# Switches.net
KiCad netlist of a schematic drawn in Altium Designer
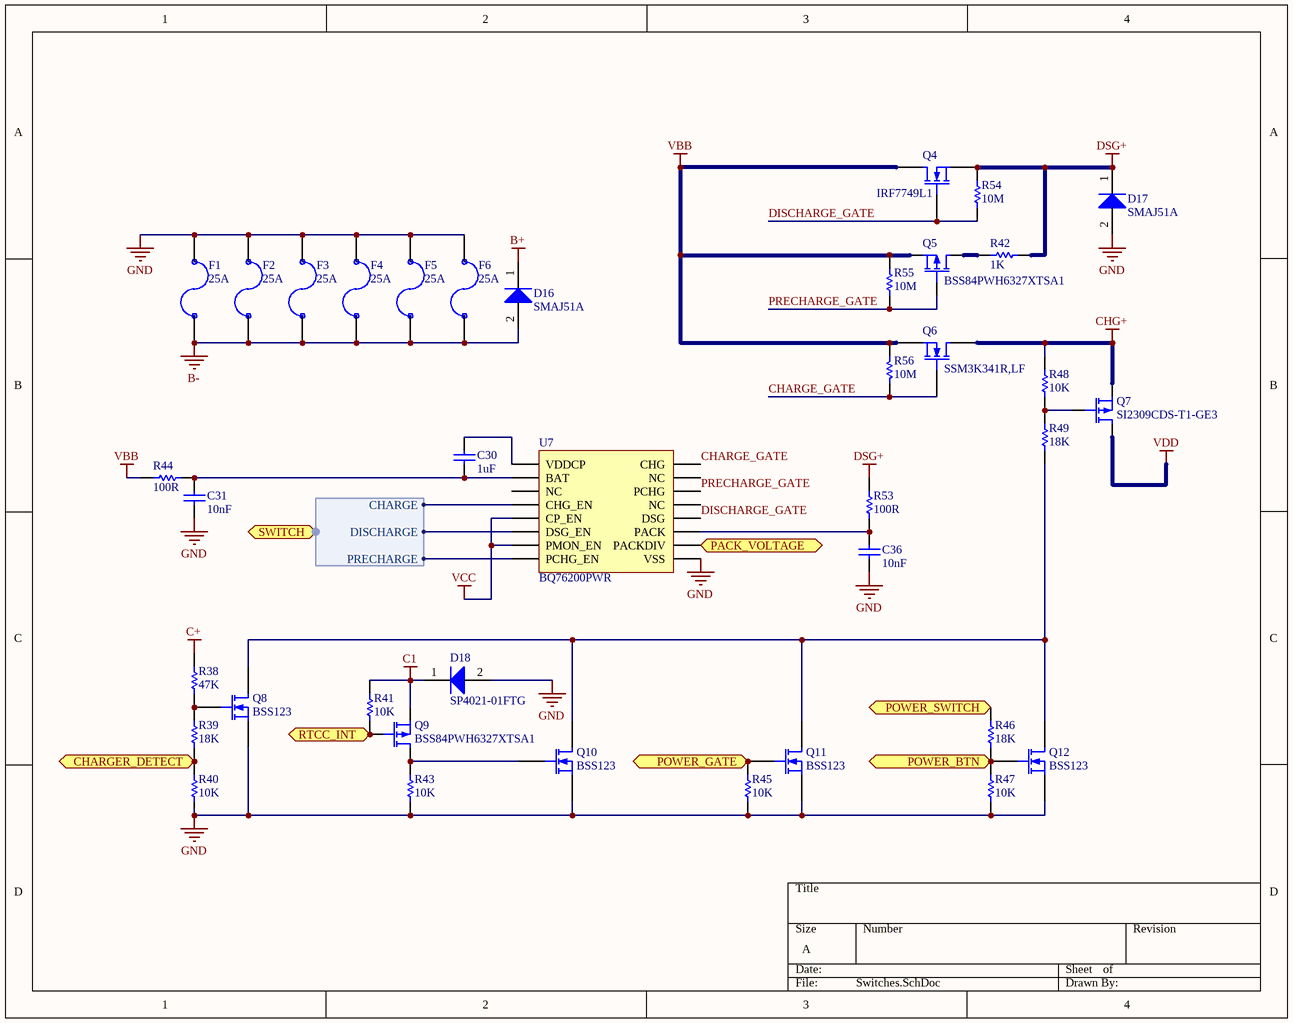
[diagram p0: Switches.SchDoc]

(export (version "E")
  (design (tool "Eeschema 10.0.6"))
  (components
    (comp (ref "C30")
      (value "1uF")
      (footprint "C0603[1608X92]")
      (description "1uF 50V 10% 0603 (1608 Metric)")
      (fields (field (name "TOLERANCE") "10%") (field (name "PARTNUMBER") "GRM188R61H105KAALD"))
      (libsource (lib "Capacitors") (part "CAP_1uF_50V_0603_10%"))
    )
    (comp (ref "C31")
      (value "10nF")
      (footprint "C0402[1005X55]")
      (description "10nF 50V 10% 0402 (1005 Metric)")
      (fields (field (name "TOLERANCE") "10%") (field (name "PARTNUMBER") "GCM155R71H103KA55D"))
      (libsource (lib "Capacitors") (part "CAP_10nF_50V_0402_10%"))
    )
    (comp (ref "C36")
      (value "10nF")
      (footprint "C0402[1005X55]")
      (description "10nF 50V 10% 0402 (1005 Metric)")
      (fields (field (name "TOLERANCE") "10%") (field (name "PARTNUMBER") "GCM155R71H103KA55D"))
      (libsource (lib "Capacitors") (part "CAP_10nF_50V_0402_10%"))
    )
    (comp (ref "D16")
      (value "SMAJ51A")
      (footprint "DO-214AC")
      (fields (field (name "PARTNUMBER") "SMAJ51A-E3/61") (field (name "MANUFACTURER") "Vishay"))
      (libsource (lib "Diodes") (part "SMAJ51A-E3/61"))
    )
    (comp (ref "D17")
      (value "SMAJ51A")
      (footprint "DO-214AC")
      (fields (field (name "PARTNUMBER") "SMAJ51A-E3/61") (field (name "MANUFACTURER") "Vishay"))
      (libsource (lib "Diodes") (part "SMAJ51A-E3/61"))
    )
    (comp (ref "D18")
      (value "SP4021-01FTG")
      (footprint "SOD-323")
      (fields (field (name "MANUFACTURER") "Littelfuse"))
      (libsource (lib "Diodes-TVS") (part "SP4021-01FTG"))
    )
    (comp (ref "F1")
      (value "FUSE 1206")
      (footprint "1206_FUSE")
      (description "Surface Mount Fuses UST 1206 FUSE 25A F")
      (fields
        (field (name "PARTNUMBER") "3413.0332.22")
        (field (name "MANUFACTURER") "Schurter")
        (field (name "CURRENT") "25A")
      )
      (libsource (lib "Components") (part "FUSE 1206"))
    )
    (comp (ref "F2")
      (value "FUSE 1206")
      (footprint "1206_FUSE")
      (description "Surface Mount Fuses UST 1206 FUSE 25A F")
      (fields
        (field (name "PARTNUMBER") "3413.0332.22")
        (field (name "MANUFACTURER") "Schurter")
        (field (name "CURRENT") "25A")
      )
      (libsource (lib "Components") (part "FUSE 1206"))
    )
    (comp (ref "F3")
      (value "FUSE 1206")
      (footprint "1206_FUSE")
      (description "Surface Mount Fuses UST 1206 FUSE 25A F")
      (fields
        (field (name "PARTNUMBER") "3413.0332.22")
        (field (name "MANUFACTURER") "Schurter")
        (field (name "CURRENT") "25A")
      )
      (libsource (lib "Components") (part "FUSE 1206"))
    )
    (comp (ref "F4")
      (value "FUSE 1206")
      (footprint "1206_FUSE")
      (description "Surface Mount Fuses UST 1206 FUSE 25A F")
      (fields
        (field (name "PARTNUMBER") "3413.0332.22")
        (field (name "MANUFACTURER") "Schurter")
        (field (name "CURRENT") "25A")
      )
      (libsource (lib "Components") (part "FUSE 1206"))
    )
    (comp (ref "F5")
      (value "FUSE 1206")
      (footprint "1206_FUSE")
      (description "Surface Mount Fuses UST 1206 FUSE 25A F")
      (fields
        (field (name "PARTNUMBER") "3413.0332.22")
        (field (name "MANUFACTURER") "Schurter")
        (field (name "CURRENT") "25A")
      )
      (libsource (lib "Components") (part "FUSE 1206"))
    )
    (comp (ref "F6")
      (value "FUSE 1206")
      (footprint "1206_FUSE")
      (description "Surface Mount Fuses UST 1206 FUSE 25A F")
      (fields
        (field (name "PARTNUMBER") "3413.0332.22")
        (field (name "MANUFACTURER") "Schurter")
        (field (name "CURRENT") "25A")
      )
      (libsource (lib "Components") (part "FUSE 1206"))
    )
    (comp (ref "Q4")
      (value "IRF7749L1")
      (footprint "DIRECTFET-9")
      (description "N-Channel MOSFET")
      (fields
        (field (name "PARTNUMBER") "IRF7749L1TRPBF")
        (field (name "MANUFACTURER") "Infineon Technologies")
      )
      (libsource (lib "MOSFETs") (part "IRF7749L2"))
    )
    (comp (ref "Q5")
      (value "BSS84PWH6327XTSA1")
      (footprint "SOT323-3")
      (description "P-Channel MOSFET")
      (fields (field (name "MANUFACTURER") "Infineon"))
      (libsource (lib "MOSFETs") (part "BSS84PW H6327"))
    )
    (comp (ref "Q6")
      (value "SSM3K341R,LF")
      (footprint "SOT23-3")
      (description "N-Channel MOSFET")
      (fields (field (name "MANUFACTURER") "Toshiba"))
      (libsource (lib "MOSFETs") (part "SSM3K341R,LF"))
    )
    (comp (ref "Q7")
      (value "SI2309CDS-T1-GE3")
      (footprint "SOT23-3")
      (description "P-Channel MOSFET")
      (fields (field (name "MANUFACTURER") "Vishay"))
      (libsource (lib "MOSFETs") (part "SI2309CDS-T1-GE3"))
    )
    (comp (ref "Q8")
      (value "BSS123")
      (footprint "SOT323-3")
      (description "N-Channel MOSFET")
      (fields (field (name "PARTNUMBER") "BSS123WQ-7-F") (field (name "MANUFACTURER") "Diodes Incorporated"))
      (libsource (lib "MOSFETs") (part "BSS123WQ-7-F"))
    )
    (comp (ref "Q9")
      (value "BSS84PWH6327XTSA1")
      (footprint "SOT323-3")
      (description "P-Channel MOSFET")
      (fields (field (name "MANUFACTURER") "Infineon"))
      (libsource (lib "MOSFETs") (part "BSS84PW H6327"))
    )
    (comp (ref "Q10")
      (value "BSS123")
      (footprint "SOT323-3")
      (description "N-Channel MOSFET")
      (fields (field (name "PARTNUMBER") "BSS123WQ-7-F") (field (name "MANUFACTURER") "Diodes Incorporated"))
      (libsource (lib "MOSFETs") (part "BSS123WQ-7-F"))
    )
    (comp (ref "Q11")
      (value "BSS123")
      (footprint "SOT323-3")
      (description "N-Channel MOSFET")
      (fields (field (name "PARTNUMBER") "BSS123WQ-7-F") (field (name "MANUFACTURER") "Diodes Incorporated"))
      (libsource (lib "MOSFETs") (part "BSS123WQ-7-F"))
    )
    (comp (ref "Q12")
      (value "BSS123")
      (footprint "SOT323-3")
      (description "N-Channel MOSFET")
      (fields (field (name "PARTNUMBER") "BSS123WQ-7-F") (field (name "MANUFACTURER") "Diodes Incorporated"))
      (libsource (lib "MOSFETs") (part "BSS123WQ-7-F"))
    )
    (comp (ref "R38")
      (value "47K")
      (footprint "R0402[1005]")
      (description "47K 0.063W 1% 0402 (1005 Metric)")
      (fields (field (name "POWER") "0.063W") (field (name "TOLERANCE") "1%"))
      (libsource (lib "Resistors") (part "RES_47K_0402_1%"))
    )
    (comp (ref "R39")
      (value "18K")
      (footprint "R0402[1005]")
      (description "18K 0.063W 1% 0402 (1005 Metric)")
      (fields (field (name "TOLERANCE") "1%") (field (name "POWER") "0.063W"))
      (libsource (lib "Resistors") (part "RES_18K_0402_1%"))
    )
    (comp (ref "R40")
      (value "10K")
      (footprint "R0402[1005]")
      (description "10K 0.063W 1% 0402 (1005 Metric)")
      (fields (field (name "TOLERANCE") "1%") (field (name "POWER") "0.063W"))
      (libsource (lib "Resistors") (part "RES_10K_0402_1%"))
    )
    (comp (ref "R41")
      (value "10K")
      (footprint "R0402[1005]")
      (description "10K 0.063W 1% 0402 (1005 Metric)")
      (fields (field (name "MANUFACTURER") "KOA Speer") (field (name "PARTNUMBER") "RK73H1ETTP1002F"))
      (libsource (lib "Resistors") (part "RES_10K_0402_1%"))
    )
    (comp (ref "R42")
      (value "1K")
      (footprint "R0805[2012]")
      (description "1K 0.5W 1% 0805 (2012 Metric)")
      (fields (field (name "TOLERANCE") "1%") (field (name "POWER") "0.5W"))
      (libsource (lib "Resistors") (part "RES_1K_0805_1%"))
    )
    (comp (ref "R43")
      (value "10K")
      (footprint "R0402[1005]")
      (description "10K 0.063W 1% 0402 (1005 Metric)")
      (fields (field (name "MANUFACTURER") "KOA Speer") (field (name "PARTNUMBER") "RK73H1ETTP1002F"))
      (libsource (lib "Resistors") (part "RES_10K_0402_1%"))
    )
    (comp (ref "R44")
      (value "100R")
      (footprint "R0402[1005]")
      (description "100R 0.063W 1% 0402 (1005 Metric)")
      (fields (field (name "POWER") "0.063W") (field (name "TOLERANCE") "1%"))
      (libsource (lib "Resistors") (part "RES_100R_0402_1%"))
    )
    (comp (ref "R45")
      (value "10K")
      (footprint "R0402[1005]")
      (description "10K 0.063W 1% 0402 (1005 Metric)")
      (fields (field (name "MANUFACTURER") "KOA Speer") (field (name "PARTNUMBER") "RK73H1ETTP1002F"))
      (libsource (lib "Resistors") (part "RES_10K_0402_1%"))
    )
    (comp (ref "R46")
      (value "18K")
      (footprint "R0402[1005]")
      (description "18K 0.063W 1% 0402 (1005 Metric)")
      (fields (field (name "TOLERANCE") "1%") (field (name "POWER") "0.063W"))
      (libsource (lib "Resistors") (part "RES_18K_0402_1%"))
    )
    (comp (ref "R47")
      (value "10K")
      (footprint "R0402[1005]")
      (description "10K 0.063W 1% 0402 (1005 Metric)")
      (fields (field (name "POWER") "0.063W") (field (name "TOLERANCE") "1%"))
      (libsource (lib "Resistors") (part "RES_10K_0402_1%"))
    )
    (comp (ref "R48")
      (value "10K")
      (footprint "R0402[1005]")
      (description "10K 0.063W 1% 0402 (1005 Metric)")
      (fields (field (name "TOLERANCE") "1%") (field (name "POWER") "0.063W"))
      (libsource (lib "Resistors") (part "RES_10K_0402_1%"))
    )
    (comp (ref "R49")
      (value "18K")
      (footprint "R0402[1005]")
      (description "18K 0.063W 1% 0402 (1005 Metric)")
      (fields (field (name "POWER") "0.063W") (field (name "TOLERANCE") "1%"))
      (libsource (lib "Resistors") (part "RES_18K_0402_1%"))
    )
    (comp (ref "R53")
      (value "100R")
      (footprint "R0402[1005]")
      (description "100R 0.063W 1% 0402 (1005 Metric)")
      (fields (field (name "POWER") "0.063W") (field (name "TOLERANCE") "1%"))
      (libsource (lib "Resistors") (part "RES_100R_0402_1%"))
    )
    (comp (ref "R54")
      (value "10M")
      (footprint "R0402[1005]")
      (description "10M 0.063W 1% 0402 (1005 Metric)")
      (fields (field (name "MANUFACTURER") "KOA Speer") (field (name "PARTNUMBER") "RK73H1ETTP1005F"))
      (libsource (lib "Resistors") (part "RES_10M_0402_1%"))
    )
    (comp (ref "R55")
      (value "10M")
      (footprint "R0402[1005]")
      (description "10M 0.063W 1% 0402 (1005 Metric)")
      (fields (field (name "MANUFACTURER") "KOA Speer") (field (name "PARTNUMBER") "RK73H1ETTP1005F"))
      (libsource (lib "Resistors") (part "RES_10M_0402_1%"))
    )
    (comp (ref "R56")
      (value "10M")
      (footprint "R0402[1005]")
      (description "10M 0.063W 1% 0402 (1005 Metric)")
      (fields (field (name "MANUFACTURER") "KOA Speer") (field (name "PARTNUMBER") "RK73H1ETTP1005F"))
      (libsource (lib "Resistors") (part "RES_10M_0402_1%"))
    )
    (comp (ref "U7")
      (value "BQ76200PWR")
      (footprint "TSSOP-16")
      (description "Battery Management Fast high side NCH drive")
      (fields (field (name "MANUFACTURER") "Texas Instruments"))
      (libsource (lib "ICs") (part "BQ76200PWR"))
    )
  )
  (nets
    (net (code "2") (name "/CHARGE") (class "Default")
      (node (ref "U7") (pin "4") (pinfunction "CHG_EN_4") (pintype "passive"))
    )
    (net (code "3") (name "/CHARGER_DETECT") (class "Default")
      (node (ref "R39") (pin "1") (pinfunction "1_1") (pintype "passive"))
      (node (ref "R40") (pin "2") (pinfunction "2_2") (pintype "passive"))
    )
    (net (code "4") (name "/CHARGE_GATE") (class "Default")
      (node (ref "Q6") (pin "1") (pinfunction "G_1") (pintype "passive"))
      (node (ref "R56") (pin "1") (pinfunction "1_1") (pintype "passive"))
      (node (ref "U7") (pin "16") (pinfunction "CHG_16") (pintype "passive"))
    )
    (net (code "5") (name "/DISCHARGE") (class "Default")
      (node (ref "U7") (pin "6") (pinfunction "DSG_EN_6") (pintype "passive"))
    )
    (net (code "6") (name "/DISCHARGE_GATE") (class "Default")
      (node (ref "Q4") (pin "1") (pinfunction "G_1") (pintype "passive"))
      (node (ref "R54") (pin "1") (pinfunction "1_1") (pintype "passive"))
      (node (ref "U7") (pin "12") (pinfunction "DSG_12") (pintype "passive"))
    )
    (net (code "7") (name "/PACK_VOLTAGE") (class "Default")
      (node (ref "U7") (pin "10") (pinfunction "PACKDIV_10") (pintype "passive"))
    )
    (net (code "8") (name "/POWER_BTN") (class "Default")
      (node (ref "Q12") (pin "1") (pinfunction "G_1") (pintype "passive"))
      (node (ref "R46") (pin "1") (pinfunction "1_1") (pintype "passive"))
      (node (ref "R47") (pin "2") (pinfunction "2_2") (pintype "passive"))
    )
    (net (code "9") (name "/POWER_GATE") (class "Default")
      (node (ref "Q11") (pin "1") (pinfunction "G_1") (pintype "passive"))
      (node (ref "R45") (pin "2") (pinfunction "2_2") (pintype "passive"))
    )
    (net (code "10") (name "/POWER_SWITCH") (class "Default")
      (node (ref "R46") (pin "2") (pinfunction "2_2") (pintype "passive"))
    )
    (net (code "11") (name "/PRECHARGE") (class "Default")
      (node (ref "U7") (pin "8") (pinfunction "PCHG_EN_8") (pintype "passive"))
    )
    (net (code "12") (name "/PRECHARGE_GATE") (class "Default")
      (node (ref "Q5") (pin "1") (pinfunction "G_1") (pintype "passive"))
      (node (ref "R55") (pin "1") (pinfunction "1_1") (pintype "passive"))
      (node (ref "U7") (pin "14") (pinfunction "PCHG_14") (pintype "passive"))
    )
    (net (code "13") (name "/RTCC_INT") (class "Default")
      (node (ref "Q9") (pin "1") (pinfunction "G_1") (pintype "passive"))
      (node (ref "R41") (pin "1") (pinfunction "1_1") (pintype "passive"))
    )
    (net (code "15") (name "B+") (class "Default")
      (node (ref "D16") (pin "1") (pinfunction "K_1") (pintype "passive"))
    )
    (net (code "16") (name "B-") (class "Default")
      (node (ref "D16") (pin "2") (pinfunction "A_2") (pintype "passive"))
      (node (ref "F1") (pin "2") (pinfunction "2_2") (pintype "passive"))
      (node (ref "F2") (pin "2") (pinfunction "2_2") (pintype "passive"))
      (node (ref "F3") (pin "2") (pinfunction "2_2") (pintype "passive"))
      (node (ref "F4") (pin "2") (pinfunction "2_2") (pintype "passive"))
      (node (ref "F5") (pin "2") (pinfunction "2_2") (pintype "passive"))
      (node (ref "F6") (pin "2") (pinfunction "2_2") (pintype "passive"))
    )
    (net (code "17") (name "C+") (class "Default")
      (node (ref "R38") (pin "2") (pinfunction "2_2") (pintype "passive"))
    )
    (net (code "18") (name "C1") (class "Default")
      (node (ref "D18") (pin "1") (pinfunction "K_1") (pintype "passive"))
      (node (ref "Q9") (pin "2") (pinfunction "S_2") (pintype "passive"))
      (node (ref "R41") (pin "2") (pinfunction "2_2") (pintype "passive"))
    )
    (net (code "19") (name "CHG+") (class "Default")
      (node (ref "Q6") (pin "3") (pinfunction "D_3") (pintype "passive"))
      (node (ref "Q7") (pin "3") (pinfunction "S_3") (pintype "passive"))
      (node (ref "R48") (pin "2") (pinfunction "2_2") (pintype "passive"))
    )
    (net (code "20") (name "DSG+") (class "Default")
      (node (ref "D17") (pin "1") (pinfunction "K_1") (pintype "passive"))
      (node (ref "Q4") (pin "2") (pinfunction "S_2") (pintype "passive"))
      (node (ref "R42") (pin "1") (pinfunction "1_1") (pintype "passive"))
      (node (ref "R53") (pin "2") (pinfunction "2_2") (pintype "passive"))
      (node (ref "R54") (pin "2") (pinfunction "2_2") (pintype "passive"))
    )
    (net (code "21") (name "GND") (class "Default")
      (node (ref "C31") (pin "1") (pinfunction "1_1") (pintype "passive"))
      (node (ref "C36") (pin "1") (pinfunction "1_1") (pintype "passive"))
      (node (ref "D17") (pin "2") (pinfunction "A_2") (pintype "passive"))
      (node (ref "D18") (pin "2") (pinfunction "A_2") (pintype "passive"))
      (node (ref "F1") (pin "1") (pinfunction "1_1") (pintype "passive"))
      (node (ref "F2") (pin "1") (pinfunction "1_1") (pintype "passive"))
      (node (ref "F3") (pin "1") (pinfunction "1_1") (pintype "passive"))
      (node (ref "F4") (pin "1") (pinfunction "1_1") (pintype "passive"))
      (node (ref "F5") (pin "1") (pinfunction "1_1") (pintype "passive"))
      (node (ref "F6") (pin "1") (pinfunction "1_1") (pintype "passive"))
      (node (ref "Q10") (pin "2") (pinfunction "S_2") (pintype "passive"))
      (node (ref "Q11") (pin "2") (pinfunction "S_2") (pintype "passive"))
      (node (ref "Q12") (pin "2") (pinfunction "S_2") (pintype "passive"))
      (node (ref "Q8") (pin "2") (pinfunction "S_2") (pintype "passive"))
      (node (ref "R40") (pin "1") (pinfunction "1_1") (pintype "passive"))
      (node (ref "R43") (pin "1") (pinfunction "1_1") (pintype "passive"))
      (node (ref "R45") (pin "1") (pinfunction "1_1") (pintype "passive"))
      (node (ref "R47") (pin "1") (pinfunction "1_1") (pintype "passive"))
      (node (ref "U7") (pin "9") (pinfunction "VSS_9") (pintype "passive"))
    )
    (net (code "22") (name "Net-(Q5-D)") (class "Default")
      (node (ref "Q5") (pin "3") (pinfunction "D_3") (pintype "passive"))
      (node (ref "R42") (pin "2") (pinfunction "2_2") (pintype "passive"))
    )
    (net (code "23") (name "Net-(Q7-G)") (class "Default")
      (node (ref "Q7") (pin "1") (pinfunction "G_1") (pintype "passive"))
      (node (ref "R48") (pin "1") (pinfunction "1_1") (pintype "passive"))
      (node (ref "R49") (pin "2") (pinfunction "2_2") (pintype "passive"))
    )
    (net (code "24") (name "Net-(Q8-G)") (class "Default")
      (node (ref "Q8") (pin "1") (pinfunction "G_1") (pintype "passive"))
      (node (ref "R38") (pin "1") (pinfunction "1_1") (pintype "passive"))
      (node (ref "R39") (pin "2") (pinfunction "2_2") (pintype "passive"))
    )
    (net (code "25") (name "Net-(Q10-D)") (class "Default")
      (node (ref "Q10") (pin "3") (pinfunction "D_3") (pintype "passive"))
      (node (ref "Q11") (pin "3") (pinfunction "D_3") (pintype "passive"))
      (node (ref "Q12") (pin "3") (pinfunction "D_3") (pintype "passive"))
      (node (ref "Q8") (pin "3") (pinfunction "D_3") (pintype "passive"))
      (node (ref "R49") (pin "1") (pinfunction "1_1") (pintype "passive"))
    )
    (net (code "26") (name "Net-(Q10-G)") (class "Default")
      (node (ref "Q10") (pin "1") (pinfunction "G_1") (pintype "passive"))
      (node (ref "Q9") (pin "3") (pinfunction "D_3") (pintype "passive"))
      (node (ref "R43") (pin "2") (pinfunction "2_2") (pintype "passive"))
    )
    (net (code "27") (name "Net-(U7-BAT)") (class "Default")
      (node (ref "C30") (pin "1") (pinfunction "1_1") (pintype "passive"))
      (node (ref "C31") (pin "2") (pinfunction "2_2") (pintype "passive"))
      (node (ref "R44") (pin "2") (pinfunction "2_2") (pintype "passive"))
      (node (ref "U7") (pin "2") (pinfunction "BAT_2") (pintype "passive"))
    )
    (net (code "28") (name "Net-(U7-PACK)") (class "Default")
      (node (ref "C36") (pin "2") (pinfunction "2_2") (pintype "passive"))
      (node (ref "R53") (pin "1") (pinfunction "1_1") (pintype "passive"))
      (node (ref "U7") (pin "11") (pinfunction "PACK_11") (pintype "passive"))
    )
    (net (code "29") (name "Net-(U7-VDDCP)") (class "Default")
      (node (ref "C30") (pin "2") (pinfunction "2_2") (pintype "passive"))
      (node (ref "U7") (pin "1") (pinfunction "VDDCP_1") (pintype "passive"))
    )
    (net (code "30") (name "VBB") (class "Default")
      (node (ref "Q4") (pin "3") (pinfunction "D_3") (pintype "passive"))
      (node (ref "Q5") (pin "2") (pinfunction "S_2") (pintype "passive"))
      (node (ref "Q6") (pin "2") (pinfunction "S_2") (pintype "passive"))
      (node (ref "R44") (pin "1") (pinfunction "1_1") (pintype "passive"))
      (node (ref "R55") (pin "2") (pinfunction "2_2") (pintype "passive"))
      (node (ref "R56") (pin "2") (pinfunction "2_2") (pintype "passive"))
    )
    (net (code "31") (name "VCC") (class "Default")
      (node (ref "U7") (pin "5") (pinfunction "CP_EN_5") (pintype "passive"))
      (node (ref "U7") (pin "7") (pinfunction "PMON_EN_7") (pintype "passive"))
    )
    (net (code "32") (name "VDD") (class "Default")
      (node (ref "Q7") (pin "2") (pinfunction "D_2") (pintype "passive"))
    )
    (net (code "33") (name "unconnected-(U7-NC-Pad3)") (class "Default")
      (node (ref "U7") (pin "3") (pinfunction "NC_3") (pintype "passive"))
    )
    (net (code "34") (name "unconnected-(U7-NC-Pad13)") (class "Default")
      (node (ref "U7") (pin "13") (pinfunction "NC_13") (pintype "passive"))
    )
    (net (code "35") (name "unconnected-(U7-NC-Pad15)") (class "Default")
      (node (ref "U7") (pin "15") (pinfunction "NC_15") (pintype "passive"))
    )
  )
)
